# external_ports.net
KiCad netlist of a schematic drawn in Altium Designer
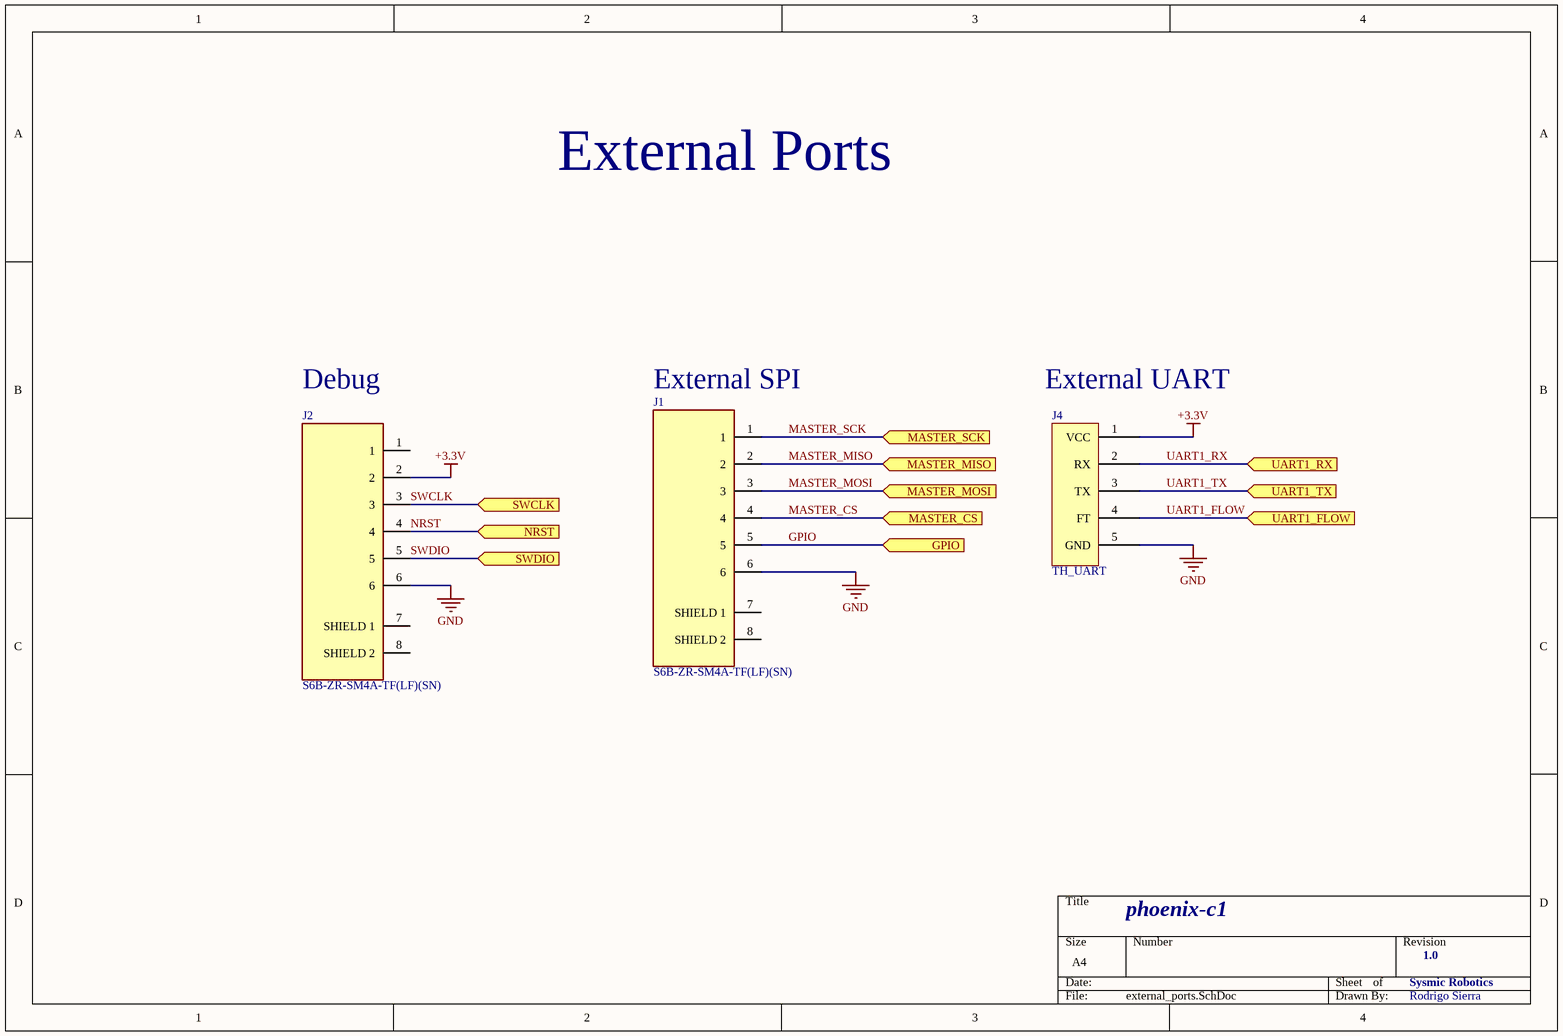
[diagram p0: external_ports.SchDoc]

(export (version "E")
  (design (tool "Eeschema 10.0.6"))
  (components
    (comp (ref "J1")
      (value "S6B-ZR-SM4A-TF(LF)(SN)")
      (footprint "FP-S6B-ZR-SM4A-TF_LF_SN-MFG")
      (description "CONN HEADER SMD R/A 6POS 1.5MM")
      (libsource (lib "CONN - CMP-17439-000151-1") (part "CMP-17439-000151-1"))
    )
    (comp (ref "J2")
      (value "S6B-ZR-SM4A-TF(LF)(SN)")
      (footprint "FP-S6B-ZR-SM4A-TF_LF_SN-MFG")
      (description "CONN HEADER SMD R/A 6POS 1.5MM")
      (libsource (lib "CONN - CMP-17439-000151-1") (part "CMP-17439-000151-1"))
    )
    (comp (ref "J4")
      (value "TH_UART")
      (footprint "CONN - TH_UART")
      (libsource (lib "CONN - TH_UART") (part "TH_UART"))
    )
  )
  (nets
    (net (code "1") (name "+3.3V") (class "Default")
      (node (ref "J2") (pin "2") (pinfunction "2_2") (pintype "passive"))
      (node (ref "J4") (pin "1") (pinfunction "VCC_1") (pintype "passive"))
    )
    (net (code "2") (name "/GPIO") (class "Default")
      (node (ref "J1") (pin "5") (pinfunction "5_5") (pintype "passive"))
    )
    (net (code "3") (name "/MASTER_CS") (class "Default")
      (node (ref "J1") (pin "4") (pinfunction "4_4") (pintype "passive"))
    )
    (net (code "4") (name "/MASTER_MISO") (class "Default")
      (node (ref "J1") (pin "2") (pinfunction "2_2") (pintype "passive"))
    )
    (net (code "5") (name "/MASTER_MOSI") (class "Default")
      (node (ref "J1") (pin "3") (pinfunction "3_3") (pintype "passive"))
    )
    (net (code "6") (name "/MASTER_SCK") (class "Default")
      (node (ref "J1") (pin "1") (pinfunction "1_1") (pintype "passive"))
    )
    (net (code "7") (name "/NRST") (class "Default")
      (node (ref "J2") (pin "4") (pinfunction "4_4") (pintype "passive"))
    )
    (net (code "8") (name "/SWCLK") (class "Default")
      (node (ref "J2") (pin "3") (pinfunction "3_3") (pintype "passive"))
    )
    (net (code "9") (name "/SWDIO") (class "Default")
      (node (ref "J2") (pin "5") (pinfunction "5_5") (pintype "passive"))
    )
    (net (code "10") (name "/UART1_FLOW") (class "Default")
      (node (ref "J4") (pin "4") (pinfunction "FT_4") (pintype "passive"))
    )
    (net (code "11") (name "/UART1_RX") (class "Default")
      (node (ref "J4") (pin "2") (pinfunction "RX_2") (pintype "passive"))
    )
    (net (code "12") (name "/UART1_TX") (class "Default")
      (node (ref "J4") (pin "3") (pinfunction "TX_3") (pintype "passive"))
    )
    (net (code "13") (name "GND") (class "Default")
      (node (ref "J1") (pin "6") (pinfunction "6_6") (pintype "passive"))
      (node (ref "J2") (pin "6") (pinfunction "6_6") (pintype "passive"))
      (node (ref "J4") (pin "5") (pinfunction "GND_5") (pintype "passive"))
    )
    (net (code "14") (name "unconnected-(J1-SHIELD_1-Pad7)") (class "Default")
      (node (ref "J1") (pin "7") (pinfunction "SHIELD_1_7") (pintype "passive"))
    )
    (net (code "15") (name "unconnected-(J1-SHIELD_2-Pad8)") (class "Default")
      (node (ref "J1") (pin "8") (pinfunction "SHIELD_2_8") (pintype "passive"))
    )
    (net (code "16") (name "unconnected-(J2-Pad1)") (class "Default")
      (node (ref "J2") (pin "1") (pinfunction "1_1") (pintype "passive"))
    )
    (net (code "17") (name "unconnected-(J2-SHIELD_1-Pad7)") (class "Default")
      (node (ref "J2") (pin "7") (pinfunction "SHIELD_1_7") (pintype "passive"))
    )
    (net (code "18") (name "unconnected-(J2-SHIELD_2-Pad8)") (class "Default")
      (node (ref "J2") (pin "8") (pinfunction "SHIELD_2_8") (pintype "passive"))
    )
  )
)
